# Sheet1.net
KiCad netlist of a schematic drawn in Altium Designer
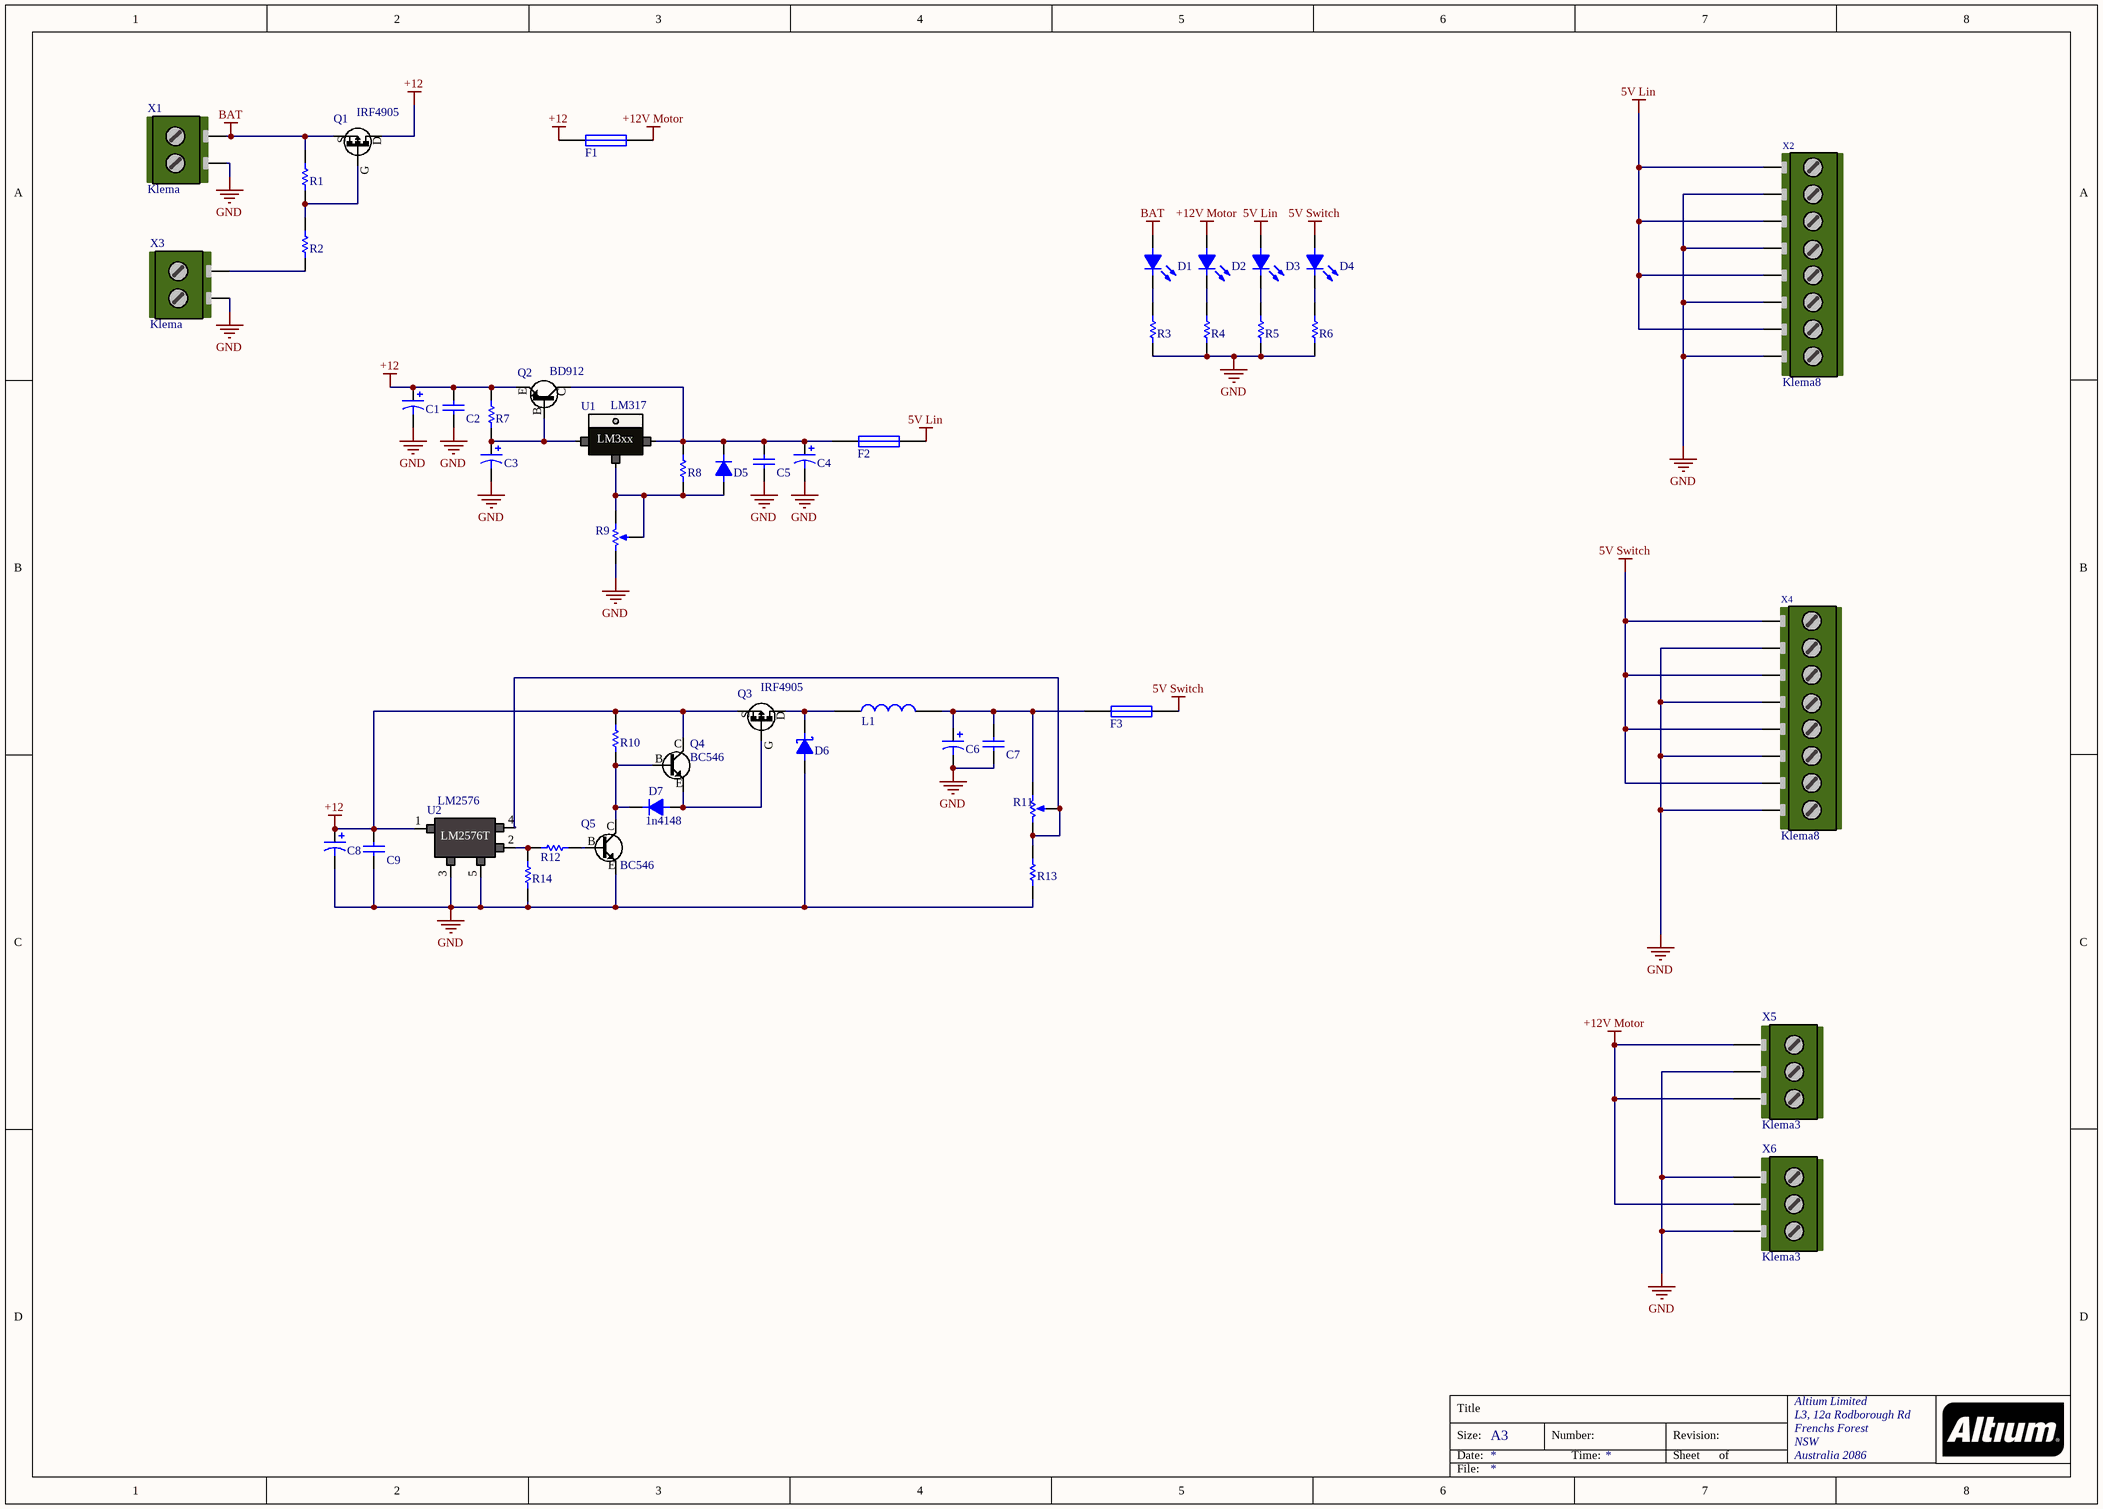
[diagram p0: Sheet1.SchDoc]

(export (version "E")
  (design (tool "Eeschema 10.0.6"))
  (components
    (comp (ref "C1")
      (value "Capacitor Electrolyt")
      (footprint "C2(elektrolit)")
      (libsource (lib "Kilex Library v2") (part "Capacitor Electrolyt"))
    )
    (comp (ref "C2")
      (value "Capacitor Ceramic")
      (footprint "C1(ceramic)")
      (libsource (lib "Kilex Library v2") (part "Capacitor Ceramic"))
    )
    (comp (ref "C3")
      (value "Capacitor Electrolyt")
      (footprint "C2-Small")
      (libsource (lib "Kilex Library v2") (part "Capacitor Electrolyt"))
    )
    (comp (ref "C4")
      (value "Capacitor Electrolyt")
      (footprint "C2(elektrolit)")
      (libsource (lib "Kilex Library v2") (part "Capacitor Electrolyt"))
    )
    (comp (ref "C5")
      (value "Capacitor Ceramic")
      (footprint "C1(ceramic)")
      (libsource (lib "Kilex Library v2") (part "Capacitor Ceramic"))
    )
    (comp (ref "C6")
      (value "Capacitor Electrolyt")
      (footprint "C2(elektrolit)")
      (libsource (lib "Kilex Library v2") (part "Capacitor Electrolyt"))
    )
    (comp (ref "C7")
      (value "Capacitor Ceramic")
      (footprint "C1(ceramic)")
      (libsource (lib "Kilex Library v2") (part "Capacitor Ceramic"))
    )
    (comp (ref "C8")
      (value "Capacitor Electrolyt")
      (footprint "C2(elektrolit)")
      (libsource (lib "Kilex Library v2") (part "Capacitor Electrolyt"))
    )
    (comp (ref "C9")
      (value "Capacitor Ceramic")
      (footprint "C1(ceramic)")
      (libsource (lib "Kilex Library v2") (part "Capacitor Ceramic"))
    )
    (comp (ref "D1")
      (value "Diode LED")
      (footprint "LED(3mm)")
      (libsource (lib "Kilex Library v2") (part "Diode LED"))
    )
    (comp (ref "D2")
      (value "Diode LED")
      (footprint "LED(3mm)")
      (libsource (lib "Kilex Library v2") (part "Diode LED"))
    )
    (comp (ref "D3")
      (value "Diode LED")
      (footprint "LED(3mm)")
      (libsource (lib "Kilex Library v2") (part "Diode LED"))
    )
    (comp (ref "D4")
      (value "Diode LED")
      (footprint "LED(3mm)")
      (libsource (lib "Kilex Library v2") (part "Diode LED"))
    )
    (comp (ref "D5")
      (value "Diode Standard")
      (footprint "D1(300milsa)")
      (libsource (lib "Kilex Library v2") (part "Diode Standard"))
    )
    (comp (ref "D6")
      (value "Diode Shottky")
      (footprint "D2(5A)")
      (libsource (lib "Kilex Library v2") (part "Diode Shottky"))
    )
    (comp (ref "D7")
      (value "1n4148")
      (footprint "D1(300milsa)")
      (libsource (lib "Kilex Library v2") (part "Diode Standard"))
    )
    (comp (ref "F1") (value "Fuse") (footprint "Osigurac") (libsource (lib "Kilex Library v2") (part "Fuse")))
    (comp (ref "F2") (value "Fuse") (footprint "Osigurac") (libsource (lib "Kilex Library v2") (part "Fuse")))
    (comp (ref "F3") (value "Fuse") (footprint "Osigurac") (libsource (lib "Kilex Library v2") (part "Fuse")))
    (comp (ref "L1")
      (value "Inductor")
      (footprint "Kalem")
      (libsource (lib "Kilex Library v2") (part "Inductor"))
    )
    (comp (ref "Q1")
      (value "IRF4905")
      (footprint "TO220")
      (libsource (lib "Kilex Library v2") (part "P-Channel MOSFET"))
    )
    (comp (ref "Q2") (value "BD912") (footprint "BD912") (libsource (lib "Kilex Library v2") (part "BD912")))
    (comp (ref "Q3")
      (value "IRF4905")
      (footprint "TO220")
      (libsource (lib "Kilex Library v2") (part "P-Channel MOSFET"))
    )
    (comp (ref "Q4")
      (value "BC546")
      (footprint "TO-92")
      (libsource (lib "Kilex Library v2") (part "Transistor NPN"))
    )
    (comp (ref "Q5")
      (value "BC546")
      (footprint "TO-92")
      (libsource (lib "Kilex Library v2") (part "Transistor NPN"))
    )
    (comp (ref "R1")
      (value "Resistor Fixed")
      (footprint "R1(300milsa)")
      (libsource (lib "Kilex Library v2") (part "Resistor Fixed"))
    )
    (comp (ref "R2")
      (value "Resistor Fixed")
      (footprint "R1(300milsa)")
      (libsource (lib "Kilex Library v2") (part "Resistor Fixed"))
    )
    (comp (ref "R3")
      (value "Resistor Fixed")
      (footprint "R1(300milsa)")
      (libsource (lib "Kilex Library v2") (part "Resistor Fixed"))
    )
    (comp (ref "R4")
      (value "Resistor Fixed")
      (footprint "R1(300milsa)")
      (libsource (lib "Kilex Library v2") (part "Resistor Fixed"))
    )
    (comp (ref "R5")
      (value "Resistor Fixed")
      (footprint "R1(300milsa)")
      (libsource (lib "Kilex Library v2") (part "Resistor Fixed"))
    )
    (comp (ref "R6")
      (value "Resistor Fixed")
      (footprint "R1(300milsa)")
      (libsource (lib "Kilex Library v2") (part "Resistor Fixed"))
    )
    (comp (ref "R7")
      (value "Resistor Fixed")
      (footprint "R1(300milsa)")
      (libsource (lib "Kilex Library v2") (part "Resistor Fixed"))
    )
    (comp (ref "R8")
      (value "Resistor Fixed")
      (footprint "R1(300milsa)")
      (libsource (lib "Kilex Library v2") (part "Resistor Fixed"))
    )
    (comp (ref "R9")
      (value "Resistor Variable")
      (footprint "TRIM")
      (libsource (lib "Kilex Library v2") (part "Resistor Variable"))
    )
    (comp (ref "R10")
      (value "Resistor Fixed")
      (footprint "R1(300milsa)")
      (libsource (lib "Kilex Library v2") (part "Resistor Fixed"))
    )
    (comp (ref "R11")
      (value "Resistor Variable")
      (footprint "TRIM")
      (libsource (lib "Kilex Library v2") (part "Resistor Variable"))
    )
    (comp (ref "R12")
      (value "Resistor Fixed")
      (footprint "R1(300milsa)")
      (libsource (lib "Kilex Library v2") (part "Resistor Fixed"))
    )
    (comp (ref "R13")
      (value "Resistor Fixed")
      (footprint "R1(300milsa)")
      (libsource (lib "Kilex Library v2") (part "Resistor Fixed"))
    )
    (comp (ref "R14")
      (value "Resistor Fixed")
      (footprint "R1(300milsa)")
      (libsource (lib "Kilex Library v2") (part "Resistor Fixed"))
    )
    (comp (ref "U1")
      (value "LM317")
      (footprint "TO220")
      (libsource (lib "Kilex Library v2") (part "LM317/LM350"))
    )
    (comp (ref "U2")
      (value "LM2576")
      (footprint "LM2576")
      (libsource (lib "Kilex Library v2") (part "LM2576"))
    )
    (comp (ref "X1") (value "Klema") (footprint "Klema") (libsource (lib "Kilex Library v2") (part "Klema")))
    (comp (ref "X2")
      (value "Klema8")
      (footprint "KLEMA8")
      (libsource (lib "Kilex Library v2") (part "Klema8"))
    )
    (comp (ref "X3") (value "Klema") (footprint "Klema") (libsource (lib "Kilex Library v2") (part "Klema")))
    (comp (ref "X4")
      (value "Klema8")
      (footprint "KLEMA8")
      (libsource (lib "Kilex Library v2") (part "Klema8"))
    )
    (comp (ref "X5")
      (value "Klema3")
      (footprint "Klema3")
      (libsource (lib "Kilex Library v2") (part "Klema3"))
    )
    (comp (ref "X6")
      (value "Klema3")
      (footprint "Klema3")
      (libsource (lib "Kilex Library v2") (part "Klema3"))
    )
  )
  (nets
    (net (code "1") (name "+12") (class "Default")
      (node (ref "C1") (pin "1") (pinfunction "1_1") (pintype "passive"))
      (node (ref "C2") (pin "1") (pinfunction "1_1") (pintype "passive"))
      (node (ref "C8") (pin "1") (pinfunction "1_1") (pintype "passive"))
      (node (ref "C9") (pin "2") (pinfunction "2_2") (pintype "passive"))
      (node (ref "F1") (pin "1") (pinfunction "1_1") (pintype "passive"))
      (node (ref "Q1") (pin "2") (pinfunction "2_2") (pintype "passive"))
      (node (ref "Q2") (pin "3") (pinfunction "3_3") (pintype "passive"))
      (node (ref "Q3") (pin "3") (pinfunction "3_3") (pintype "passive"))
      (node (ref "Q4") (pin "3") (pinfunction "3_3") (pintype "passive"))
      (node (ref "R10") (pin "2") (pinfunction "2_2") (pintype "passive"))
      (node (ref "R7") (pin "2") (pinfunction "2_2") (pintype "passive"))
      (node (ref "U2") (pin "1") (pinfunction "1_1") (pintype "passive"))
    )
    (net (code "2") (name "+12V Motor") (class "Default")
      (node (ref "D2") (pin "1") (pinfunction "A_1") (pintype "passive"))
      (node (ref "F1") (pin "2") (pinfunction "2_2") (pintype "passive"))
      (node (ref "X5") (pin "1") (pinfunction "1_1") (pintype "passive"))
      (node (ref "X5") (pin "3") (pinfunction "3_3") (pintype "passive"))
      (node (ref "X6") (pin "2") (pinfunction "2_2") (pintype "passive"))
    )
    (net (code "3") (name "5V Lin") (class "Default")
      (node (ref "D3") (pin "1") (pinfunction "A_1") (pintype "passive"))
      (node (ref "F2") (pin "2") (pinfunction "2_2") (pintype "passive"))
      (node (ref "X2") (pin "1") (pinfunction "1_1") (pintype "passive"))
      (node (ref "X2") (pin "3") (pinfunction "3_3") (pintype "passive"))
      (node (ref "X2") (pin "5") (pinfunction "5_5") (pintype "passive"))
      (node (ref "X2") (pin "7") (pinfunction "7_7") (pintype "passive"))
    )
    (net (code "4") (name "5V Switch") (class "Default")
      (node (ref "D4") (pin "1") (pinfunction "A_1") (pintype "passive"))
      (node (ref "F3") (pin "2") (pinfunction "2_2") (pintype "passive"))
      (node (ref "X4") (pin "1") (pinfunction "1_1") (pintype "passive"))
      (node (ref "X4") (pin "3") (pinfunction "3_3") (pintype "passive"))
      (node (ref "X4") (pin "5") (pinfunction "5_5") (pintype "passive"))
      (node (ref "X4") (pin "7") (pinfunction "7_7") (pintype "passive"))
    )
    (net (code "5") (name "BAT") (class "Default")
      (node (ref "D1") (pin "1") (pinfunction "A_1") (pintype "passive"))
      (node (ref "Q1") (pin "3") (pinfunction "3_3") (pintype "passive"))
      (node (ref "R1") (pin "2") (pinfunction "2_2") (pintype "passive"))
      (node (ref "X1") (pin "2") (pinfunction "2_2") (pintype "passive"))
    )
    (net (code "6") (name "GND") (class "Default")
      (node (ref "C1") (pin "2") (pinfunction "2_2") (pintype "passive"))
      (node (ref "C2") (pin "2") (pinfunction "2_2") (pintype "passive"))
      (node (ref "C3") (pin "2") (pinfunction "2_2") (pintype "passive"))
      (node (ref "C4") (pin "2") (pinfunction "2_2") (pintype "passive"))
      (node (ref "C5") (pin "2") (pinfunction "2_2") (pintype "passive"))
      (node (ref "C6") (pin "2") (pinfunction "2_2") (pintype "passive"))
      (node (ref "C7") (pin "1") (pinfunction "1_1") (pintype "passive"))
      (node (ref "C8") (pin "2") (pinfunction "2_2") (pintype "passive"))
      (node (ref "C9") (pin "1") (pinfunction "1_1") (pintype "passive"))
      (node (ref "D6") (pin "1") (pinfunction "A_1") (pintype "passive"))
      (node (ref "Q5") (pin "2") (pinfunction "2_2") (pintype "passive"))
      (node (ref "R13") (pin "1") (pinfunction "1_1") (pintype "passive"))
      (node (ref "R14") (pin "1") (pinfunction "1_1") (pintype "passive"))
      (node (ref "R3") (pin "1") (pinfunction "1_1") (pintype "passive"))
      (node (ref "R4") (pin "1") (pinfunction "1_1") (pintype "passive"))
      (node (ref "R5") (pin "1") (pinfunction "1_1") (pintype "passive"))
      (node (ref "R6") (pin "1") (pinfunction "1_1") (pintype "passive"))
      (node (ref "R9") (pin "3") (pinfunction "BOT_3") (pintype "passive"))
      (node (ref "U2") (pin "3") (pinfunction "3_3") (pintype "passive"))
      (node (ref "U2") (pin "5") (pinfunction "5_5") (pintype "passive"))
      (node (ref "X1") (pin "1") (pinfunction "1_1") (pintype "passive"))
      (node (ref "X2") (pin "2") (pinfunction "2_2") (pintype "passive"))
      (node (ref "X2") (pin "4") (pinfunction "4_4") (pintype "passive"))
      (node (ref "X2") (pin "6") (pinfunction "6_6") (pintype "passive"))
      (node (ref "X2") (pin "8") (pinfunction "8_8") (pintype "passive"))
      (node (ref "X3") (pin "1") (pinfunction "1_1") (pintype "passive"))
      (node (ref "X4") (pin "2") (pinfunction "2_2") (pintype "passive"))
      (node (ref "X4") (pin "4") (pinfunction "4_4") (pintype "passive"))
      (node (ref "X4") (pin "6") (pinfunction "6_6") (pintype "passive"))
      (node (ref "X4") (pin "8") (pinfunction "8_8") (pintype "passive"))
      (node (ref "X5") (pin "2") (pinfunction "2_2") (pintype "passive"))
      (node (ref "X6") (pin "1") (pinfunction "1_1") (pintype "passive"))
      (node (ref "X6") (pin "3") (pinfunction "3_3") (pintype "passive"))
    )
    (net (code "7") (name "Net-(C3-Pad1)") (class "Default")
      (node (ref "C3") (pin "1") (pinfunction "1_1") (pintype "passive"))
      (node (ref "Q2") (pin "1") (pinfunction "1_1") (pintype "passive"))
      (node (ref "R7") (pin "1") (pinfunction "1_1") (pintype "passive"))
      (node (ref "U1") (pin "3") (pinfunction "3_3") (pintype "passive"))
    )
    (net (code "8") (name "Net-(D1-K)") (class "Default")
      (node (ref "D1") (pin "2") (pinfunction "K_2") (pintype "passive"))
      (node (ref "R3") (pin "2") (pinfunction "2_2") (pintype "passive"))
    )
    (net (code "9") (name "Net-(D2-K)") (class "Default")
      (node (ref "D2") (pin "2") (pinfunction "K_2") (pintype "passive"))
      (node (ref "R4") (pin "2") (pinfunction "2_2") (pintype "passive"))
    )
    (net (code "10") (name "Net-(D3-K)") (class "Default")
      (node (ref "D3") (pin "2") (pinfunction "K_2") (pintype "passive"))
      (node (ref "R5") (pin "2") (pinfunction "2_2") (pintype "passive"))
    )
    (net (code "11") (name "Net-(D4-K)") (class "Default")
      (node (ref "D4") (pin "2") (pinfunction "K_2") (pintype "passive"))
      (node (ref "R6") (pin "2") (pinfunction "2_2") (pintype "passive"))
    )
    (net (code "12") (name "Net-(D5-A)") (class "Default")
      (node (ref "D5") (pin "1") (pinfunction "A_1") (pintype "passive"))
      (node (ref "R8") (pin "1") (pinfunction "1_1") (pintype "passive"))
      (node (ref "R9") (pin "1") (pinfunction "TOP_1") (pintype "passive"))
      (node (ref "R9") (pin "2") (pinfunction "TAP_2") (pintype "passive"))
      (node (ref "U1") (pin "1") (pinfunction "1_1") (pintype "passive"))
    )
    (net (code "13") (name "Net-(D5-K)") (class "Default")
      (node (ref "C4") (pin "1") (pinfunction "1_1") (pintype "passive"))
      (node (ref "C5") (pin "1") (pinfunction "1_1") (pintype "passive"))
      (node (ref "D5") (pin "2") (pinfunction "K_2") (pintype "passive"))
      (node (ref "F2") (pin "1") (pinfunction "1_1") (pintype "passive"))
      (node (ref "Q2") (pin "2") (pinfunction "2_2") (pintype "passive"))
      (node (ref "R8") (pin "2") (pinfunction "2_2") (pintype "passive"))
      (node (ref "U1") (pin "2") (pinfunction "2_2") (pintype "passive"))
    )
    (net (code "14") (name "Net-(D6-K)") (class "Default")
      (node (ref "D6") (pin "2") (pinfunction "K_2") (pintype "passive"))
      (node (ref "L1") (pin "1") (pinfunction "1_1") (pintype "passive"))
      (node (ref "Q3") (pin "2") (pinfunction "2_2") (pintype "passive"))
    )
    (net (code "15") (name "Net-(D7-A)") (class "Default")
      (node (ref "D7") (pin "1") (pinfunction "A_1") (pintype "passive"))
      (node (ref "Q3") (pin "1") (pinfunction "1_1") (pintype "passive"))
      (node (ref "Q4") (pin "2") (pinfunction "2_2") (pintype "passive"))
    )
    (net (code "16") (name "Net-(D7-K)") (class "Default")
      (node (ref "D7") (pin "2") (pinfunction "K_2") (pintype "passive"))
      (node (ref "Q4") (pin "1") (pinfunction "1_1") (pintype "passive"))
      (node (ref "Q5") (pin "3") (pinfunction "3_3") (pintype "passive"))
      (node (ref "R10") (pin "1") (pinfunction "1_1") (pintype "passive"))
    )
    (net (code "17") (name "Net-(Q1-Pad1)") (class "Default")
      (node (ref "Q1") (pin "1") (pinfunction "1_1") (pintype "passive"))
      (node (ref "R1") (pin "1") (pinfunction "1_1") (pintype "passive"))
      (node (ref "R2") (pin "2") (pinfunction "2_2") (pintype "passive"))
    )
    (net (code "18") (name "Net-(Q5-Pad1)") (class "Default")
      (node (ref "Q5") (pin "1") (pinfunction "1_1") (pintype "passive"))
      (node (ref "R12") (pin "2") (pinfunction "2_2") (pintype "passive"))
    )
    (net (code "19") (name "Net-(R2-Pad1)") (class "Default")
      (node (ref "R2") (pin "1") (pinfunction "1_1") (pintype "passive"))
      (node (ref "X3") (pin "2") (pinfunction "2_2") (pintype "passive"))
    )
    (net (code "20") (name "Net-(R11-BOT)") (class "Default")
      (node (ref "R11") (pin "2") (pinfunction "TAP_2") (pintype "passive"))
      (node (ref "R11") (pin "3") (pinfunction "BOT_3") (pintype "passive"))
      (node (ref "R13") (pin "2") (pinfunction "2_2") (pintype "passive"))
      (node (ref "U2") (pin "4") (pinfunction "4_4") (pintype "passive"))
    )
    (net (code "21") (name "Net-(R11-TOP)") (class "Default")
      (node (ref "C6") (pin "1") (pinfunction "1_1") (pintype "passive"))
      (node (ref "C7") (pin "2") (pinfunction "2_2") (pintype "passive"))
      (node (ref "F3") (pin "1") (pinfunction "1_1") (pintype "passive"))
      (node (ref "L1") (pin "2") (pinfunction "2_2") (pintype "passive"))
      (node (ref "R11") (pin "1") (pinfunction "TOP_1") (pintype "passive"))
    )
    (net (code "22") (name "Net-(R12-Pad1)") (class "Default")
      (node (ref "R12") (pin "1") (pinfunction "1_1") (pintype "passive"))
      (node (ref "R14") (pin "2") (pinfunction "2_2") (pintype "passive"))
      (node (ref "U2") (pin "2") (pinfunction "2_2") (pintype "passive"))
    )
  )
)
